# SCH_h_ty_2025829_stm32__2025-11-28.net
KiCad netlist of a schematic drawn in EasyEDA
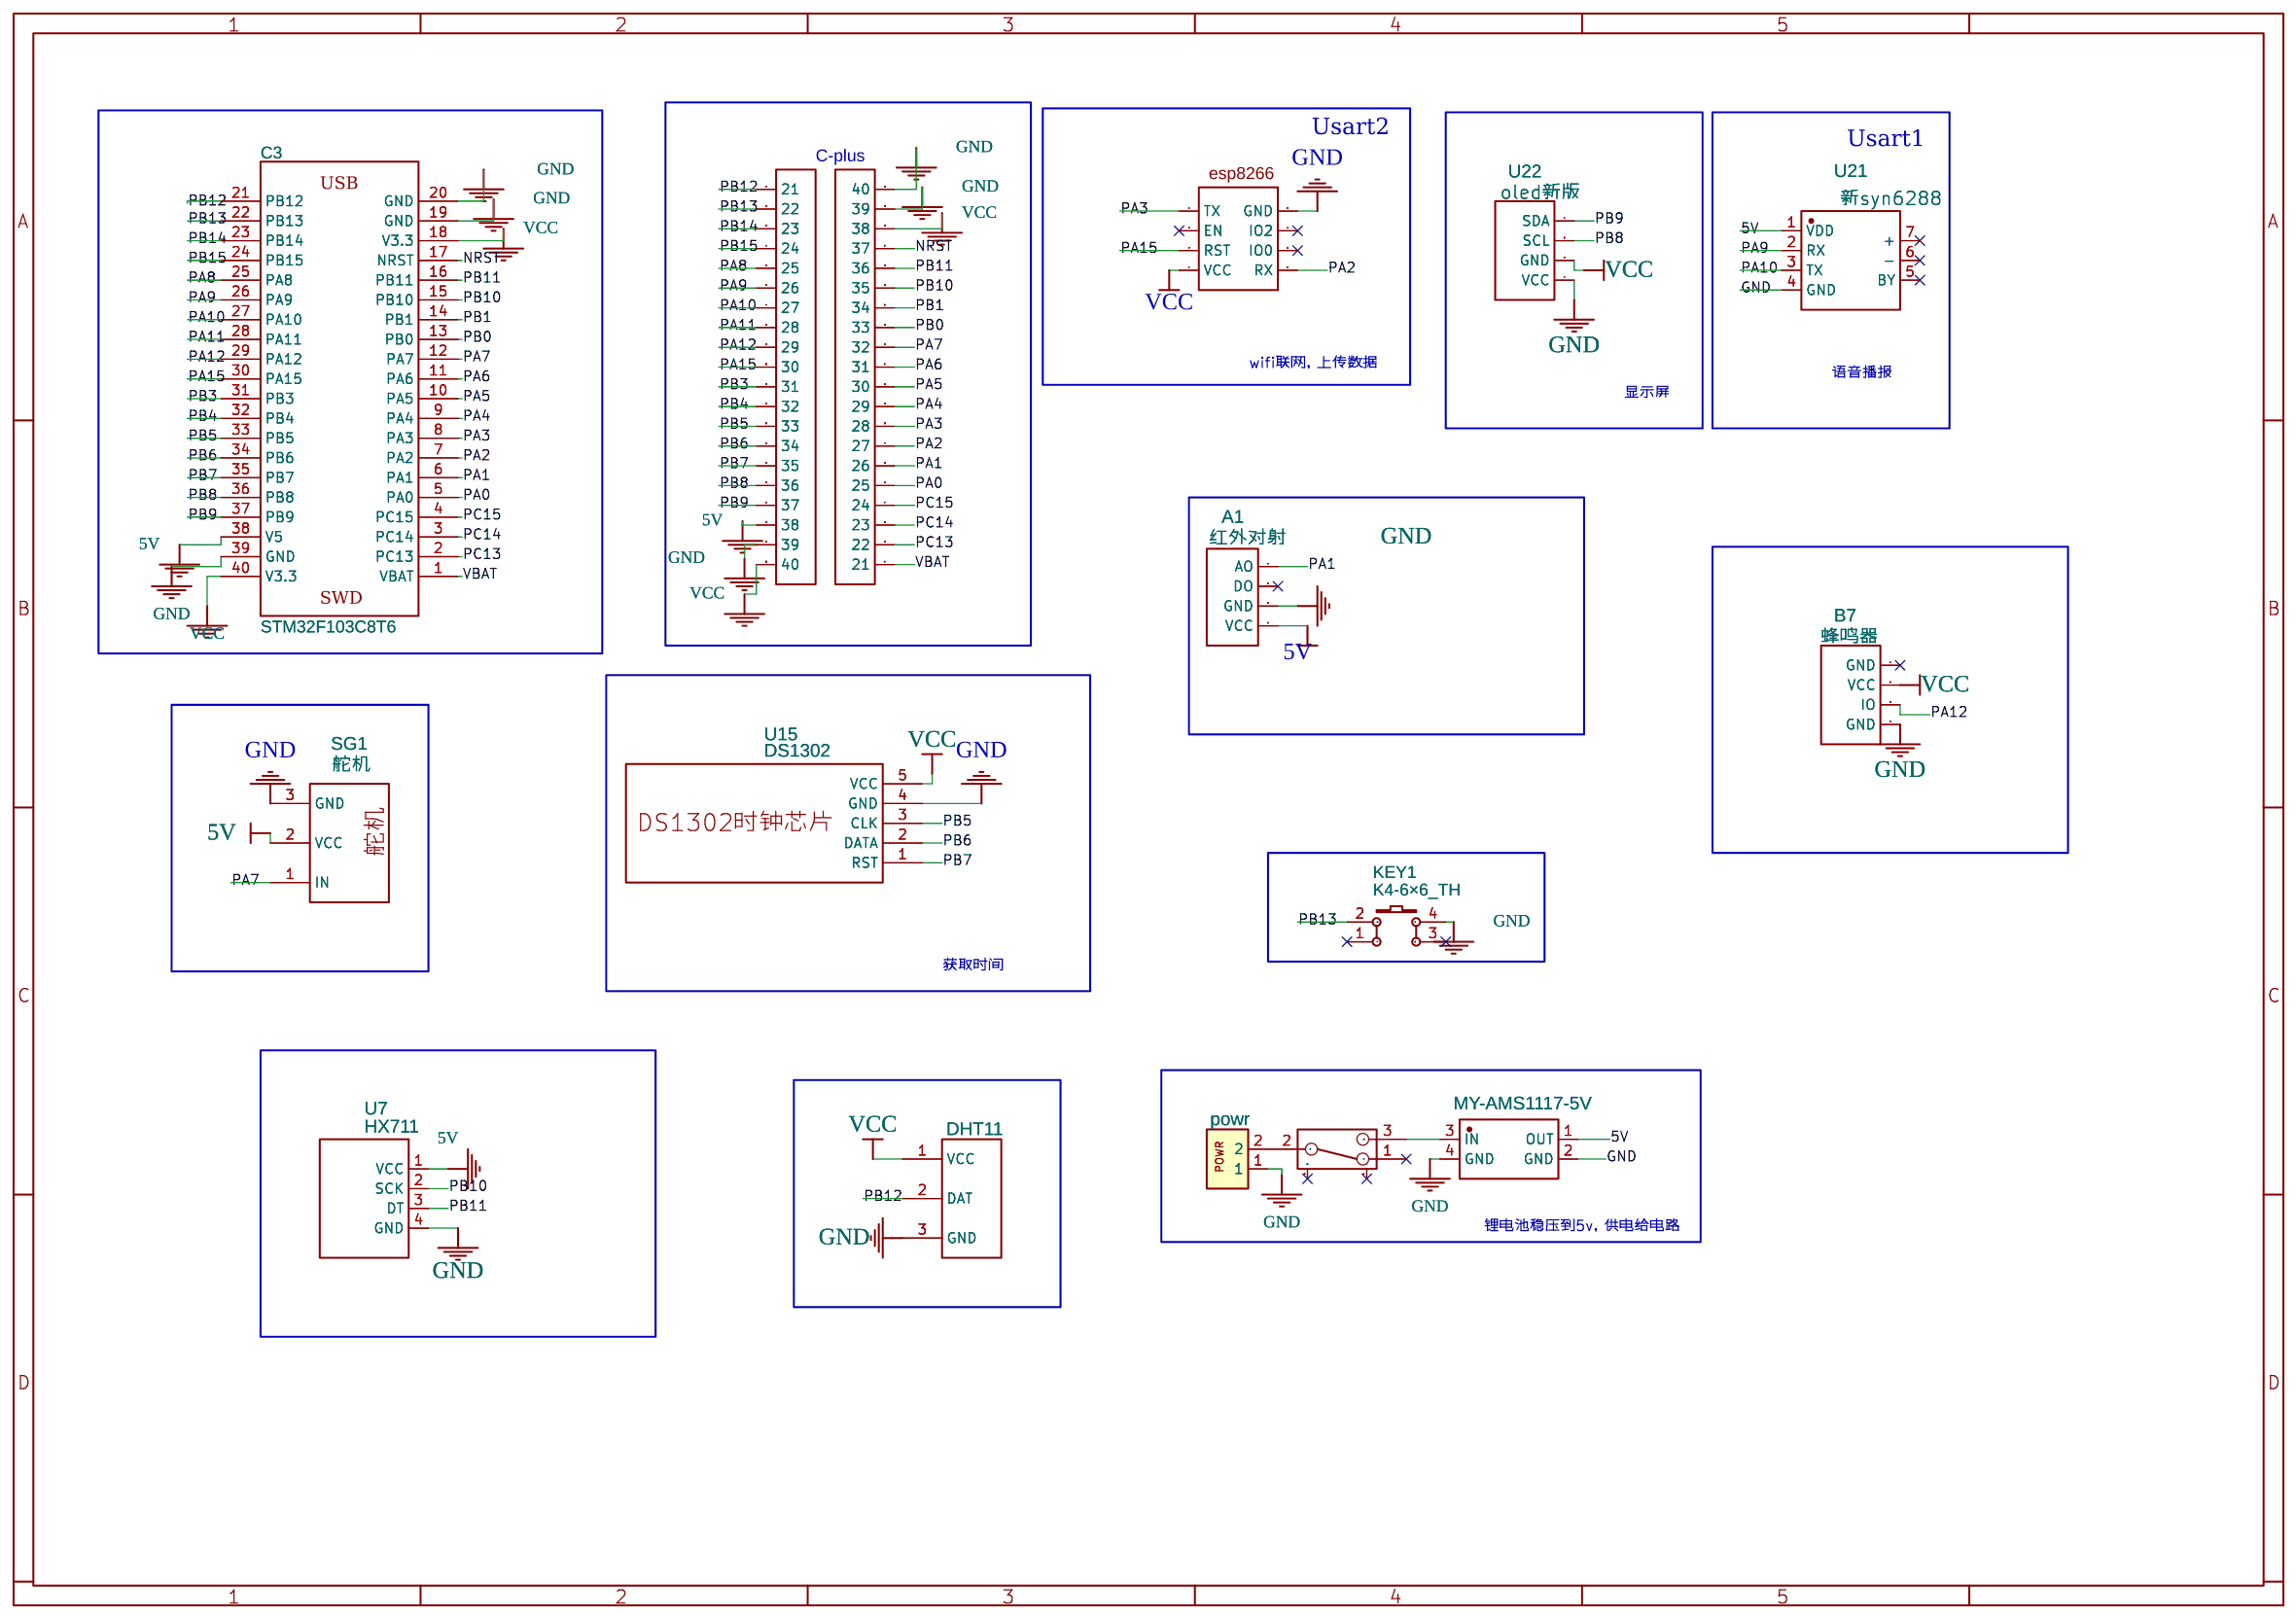
[diagram p0: schematic sheet]

(export (version "E")
  (design (tool "Eeschema 10.0.6"))
  (components
    (comp (ref "A1") (value "红外对射") (libsource (lib "") (part "ADC4P")))
    (comp (ref "B7") (value "蜂鸣器") (libsource (lib "") (part "通用3.3")))
    (comp (ref "C3") (value "STM32F103C8T6") (libsource (lib "") (part "STM32F103C8T6最小系统模块")))
    (comp (ref "DHT11") (value "DHT11模块") (libsource (lib "") (part "DHT11模块")))
    (comp (ref "H2") (value "HDR-F-2.54_1x20") (libsource (lib "") (part "HDR-F-2.54_1x20_1")))
    (comp (ref "H3") (value "HDR-F-2.54_1x20") (libsource (lib "") (part "HDR-F-2.54_1x20")))
    (comp (ref "KEY1")
      (value "K4-6×6_TH")
      (fields (field (name "Manufacturer Part") "K2-1102DP-E4SW-04") (field (name "Manufacturer") "韩国韩荣"))
      (libsource (lib "") (part "K4-6×6_TH"))
    )
    (comp (ref "SG1") (value "舵机") (libsource (lib "") (part "舵机")))
    (comp (ref "SW2")
      (value "SK-12E12-G5")
      (fields (field (name "Manufacturer") "Rectangular Connectors - Contacts"))
      (libsource (lib "") (part "SK-12E12-G5"))
    )
    (comp (ref "U2") (value "powr") (libsource (lib "") (part "powr")))
    (comp (ref "U7") (value "HX711") (libsource (lib "") (part "HX711")))
    (comp (ref "U9") (value "esp8266") (libsource (lib "") (part "esp8266")))
    (comp (ref "U12") (value "MY-AMS1117-5V") (libsource (lib "") (part "MY-AMS1117-5V")))
    (comp (ref "U15") (value "DS1302") (libsource (lib "") (part "DS1302")))
    (comp (ref "U21") (value "新syn6288") (libsource (lib "") (part "新syn6288")))
    (comp (ref "U22") (value "oled新版") (libsource (lib "") (part "HDR-M-2.54_1x4")))
  )
  (nets
    (net (code "1") (name "/NRST") (class "Default")
      (node (ref "C3") (pin "17") (pinfunction "NRST_17") (pintype "unspecified"))
      (node (ref "H3") (pin "17") (pinfunction "37_17") (pintype "unspecified"))
    )
    (net (code "2") (name "/PA0") (class "Default")
      (node (ref "C3") (pin "5") (pinfunction "PA0_5") (pintype "unspecified"))
      (node (ref "H3") (pin "5") (pinfunction "25_5") (pintype "unspecified"))
    )
    (net (code "3") (name "/PA1") (class "Default")
      (node (ref "A1") (pin "4") (pinfunction "AO_4") (pintype "unspecified"))
      (node (ref "C3") (pin "6") (pinfunction "PA1_6") (pintype "unspecified"))
      (node (ref "H3") (pin "6") (pinfunction "26_6") (pintype "unspecified"))
    )
    (net (code "4") (name "/PA2") (class "Default")
      (node (ref "C3") (pin "7") (pinfunction "PA2_7") (pintype "unspecified"))
      (node (ref "H3") (pin "7") (pinfunction "27_7") (pintype "unspecified"))
      (node (ref "U9") (pin "8") (pinfunction "RX_8") (pintype "unspecified"))
    )
    (net (code "5") (name "/PA3") (class "Default")
      (node (ref "C3") (pin "8") (pinfunction "PA3_8") (pintype "unspecified"))
      (node (ref "H3") (pin "8") (pinfunction "28_8") (pintype "unspecified"))
      (node (ref "U9") (pin "1") (pinfunction "TX_1") (pintype "unspecified"))
    )
    (net (code "6") (name "/PA4") (class "Default")
      (node (ref "C3") (pin "9") (pinfunction "PA4_9") (pintype "unspecified"))
      (node (ref "H3") (pin "9") (pinfunction "29_9") (pintype "unspecified"))
    )
    (net (code "7") (name "/PA5") (class "Default")
      (node (ref "C3") (pin "10") (pinfunction "PA5_10") (pintype "unspecified"))
      (node (ref "H3") (pin "10") (pinfunction "30_10") (pintype "unspecified"))
    )
    (net (code "8") (name "/PA6") (class "Default")
      (node (ref "C3") (pin "11") (pinfunction "PA6_11") (pintype "unspecified"))
      (node (ref "H3") (pin "11") (pinfunction "31_11") (pintype "unspecified"))
    )
    (net (code "9") (name "/PA7") (class "Default")
      (node (ref "C3") (pin "12") (pinfunction "PA7_12") (pintype "unspecified"))
      (node (ref "H3") (pin "12") (pinfunction "32_12") (pintype "unspecified"))
      (node (ref "SG1") (pin "1") (pinfunction "IN_1") (pintype "unspecified"))
    )
    (net (code "10") (name "/PA8") (class "Default")
      (node (ref "C3") (pin "25") (pinfunction "PA8_25") (pintype "unspecified"))
      (node (ref "H2") (pin "5") (pinfunction "25_5") (pintype "unspecified"))
    )
    (net (code "11") (name "/PA9") (class "Default")
      (node (ref "C3") (pin "26") (pinfunction "PA9_26") (pintype "unspecified"))
      (node (ref "H2") (pin "6") (pinfunction "26_6") (pintype "unspecified"))
      (node (ref "U21") (pin "2") (pinfunction "RX_2") (pintype "unspecified"))
    )
    (net (code "12") (name "/PA10") (class "Default")
      (node (ref "C3") (pin "27") (pinfunction "PA10_27") (pintype "unspecified"))
      (node (ref "H2") (pin "7") (pinfunction "27_7") (pintype "unspecified"))
      (node (ref "U21") (pin "3") (pinfunction "TX_3") (pintype "unspecified"))
    )
    (net (code "13") (name "/PA11") (class "Default")
      (node (ref "C3") (pin "28") (pinfunction "PA11_28") (pintype "unspecified"))
      (node (ref "H2") (pin "8") (pinfunction "28_8") (pintype "unspecified"))
    )
    (net (code "14") (name "/PA12") (class "Default")
      (node (ref "B7") (pin "2") (pinfunction "IO_2") (pintype "unspecified"))
      (node (ref "C3") (pin "29") (pinfunction "PA12_29") (pintype "unspecified"))
      (node (ref "H2") (pin "9") (pinfunction "29_9") (pintype "unspecified"))
    )
    (net (code "15") (name "/PA15") (class "Default")
      (node (ref "C3") (pin "30") (pinfunction "PA15_30") (pintype "unspecified"))
      (node (ref "H2") (pin "10") (pinfunction "30_10") (pintype "unspecified"))
      (node (ref "U9") (pin "5") (pinfunction "RST_5") (pintype "unspecified"))
    )
    (net (code "16") (name "/PB0") (class "Default")
      (node (ref "C3") (pin "13") (pinfunction "PB0_13") (pintype "unspecified"))
      (node (ref "H3") (pin "13") (pinfunction "33_13") (pintype "unspecified"))
    )
    (net (code "17") (name "/PB1") (class "Default")
      (node (ref "C3") (pin "14") (pinfunction "PB1_14") (pintype "unspecified"))
      (node (ref "H3") (pin "14") (pinfunction "34_14") (pintype "unspecified"))
    )
    (net (code "18") (name "/PB3") (class "Default")
      (node (ref "C3") (pin "31") (pinfunction "PB3_31") (pintype "unspecified"))
      (node (ref "H2") (pin "11") (pinfunction "31_11") (pintype "unspecified"))
    )
    (net (code "19") (name "/PB4") (class "Default")
      (node (ref "C3") (pin "32") (pinfunction "PB4_32") (pintype "unspecified"))
      (node (ref "H2") (pin "12") (pinfunction "32_12") (pintype "unspecified"))
    )
    (net (code "20") (name "/PB5") (class "Default")
      (node (ref "C3") (pin "33") (pinfunction "PB5_33") (pintype "unspecified"))
      (node (ref "H2") (pin "13") (pinfunction "33_13") (pintype "unspecified"))
      (node (ref "U15") (pin "3") (pinfunction "CLK_3") (pintype "unspecified"))
    )
    (net (code "21") (name "/PB6") (class "Default")
      (node (ref "C3") (pin "34") (pinfunction "PB6_34") (pintype "unspecified"))
      (node (ref "H2") (pin "14") (pinfunction "34_14") (pintype "unspecified"))
      (node (ref "U15") (pin "2") (pinfunction "DATA_2") (pintype "unspecified"))
    )
    (net (code "22") (name "/PB7") (class "Default")
      (node (ref "C3") (pin "35") (pinfunction "PB7_35") (pintype "unspecified"))
      (node (ref "H2") (pin "15") (pinfunction "35_15") (pintype "unspecified"))
      (node (ref "U15") (pin "1") (pinfunction "RST_1") (pintype "unspecified"))
    )
    (net (code "23") (name "/PB8") (class "Default")
      (node (ref "C3") (pin "36") (pinfunction "PB8_36") (pintype "unspecified"))
      (node (ref "H2") (pin "16") (pinfunction "36_16") (pintype "unspecified"))
      (node (ref "U22") (pin "3") (pinfunction "SCL_3") (pintype "unspecified"))
    )
    (net (code "24") (name "/PB9") (class "Default")
      (node (ref "C3") (pin "37") (pinfunction "PB9_37") (pintype "unspecified"))
      (node (ref "H2") (pin "17") (pinfunction "37_17") (pintype "unspecified"))
      (node (ref "U22") (pin "4") (pinfunction "SDA_4") (pintype "unspecified"))
    )
    (net (code "25") (name "/PB10") (class "Default")
      (node (ref "C3") (pin "15") (pinfunction "PB10_15") (pintype "unspecified"))
      (node (ref "H3") (pin "15") (pinfunction "35_15") (pintype "unspecified"))
      (node (ref "U7") (pin "2") (pinfunction "SCK_2") (pintype "unspecified"))
    )
    (net (code "26") (name "/PB11") (class "Default")
      (node (ref "C3") (pin "16") (pinfunction "PB11_16") (pintype "unspecified"))
      (node (ref "H3") (pin "16") (pinfunction "36_16") (pintype "unspecified"))
      (node (ref "U7") (pin "3") (pinfunction "DT_3") (pintype "unspecified"))
    )
    (net (code "27") (name "/PB12") (class "Default")
      (node (ref "C3") (pin "21") (pinfunction "PB12_21") (pintype "unspecified"))
      (node (ref "DHT11") (pin "2") (pinfunction "DAT_2") (pintype "unspecified"))
      (node (ref "H2") (pin "1") (pinfunction "21_1") (pintype "unspecified"))
    )
    (net (code "28") (name "/PB13") (class "Default")
      (node (ref "C3") (pin "22") (pinfunction "PB13_22") (pintype "unspecified"))
      (node (ref "H2") (pin "2") (pinfunction "22_2") (pintype "unspecified"))
      (node (ref "KEY1") (pin "2") (pinfunction "2_2") (pintype "unspecified"))
    )
    (net (code "29") (name "/PB14") (class "Default")
      (node (ref "C3") (pin "23") (pinfunction "PB14_23") (pintype "unspecified"))
      (node (ref "H2") (pin "3") (pinfunction "23_3") (pintype "unspecified"))
    )
    (net (code "30") (name "/PB15") (class "Default")
      (node (ref "C3") (pin "24") (pinfunction "PB15_24") (pintype "unspecified"))
      (node (ref "H2") (pin "4") (pinfunction "24_4") (pintype "unspecified"))
    )
    (net (code "31") (name "/PC13") (class "Default")
      (node (ref "C3") (pin "2") (pinfunction "PC13_2") (pintype "unspecified"))
      (node (ref "H3") (pin "2") (pinfunction "22_2") (pintype "unspecified"))
    )
    (net (code "32") (name "/PC14") (class "Default")
      (node (ref "C3") (pin "3") (pinfunction "PC14_3") (pintype "unspecified"))
      (node (ref "H3") (pin "3") (pinfunction "23_3") (pintype "unspecified"))
    )
    (net (code "33") (name "/PC15") (class "Default")
      (node (ref "C3") (pin "4") (pinfunction "PC15_4") (pintype "unspecified"))
      (node (ref "H3") (pin "4") (pinfunction "24_4") (pintype "unspecified"))
    )
    (net (code "34") (name "/VBAT") (class "Default")
      (node (ref "C3") (pin "1") (pinfunction "VBAT_1") (pintype "unspecified"))
      (node (ref "H3") (pin "1") (pinfunction "21_1") (pintype "unspecified"))
    )
    (net (code "35") (name "5V") (class "Default")
      (node (ref "A1") (pin "1") (pinfunction "VCC_1") (pintype "unspecified"))
      (node (ref "C3") (pin "38") (pinfunction "V5_38") (pintype "unspecified"))
      (node (ref "H2") (pin "18") (pinfunction "38_18") (pintype "unspecified"))
      (node (ref "SG1") (pin "2") (pinfunction "VCC_2") (pintype "unspecified"))
      (node (ref "U12") (pin "1") (pinfunction "OUT_1") (pintype "unspecified"))
      (node (ref "U21") (pin "1") (pinfunction "VDD_1") (pintype "unspecified"))
      (node (ref "U7") (pin "1") (pinfunction "VCC_1") (pintype "unspecified"))
    )
    (net (code "36") (name "GND") (class "Default")
      (node (ref "A1") (pin "2") (pinfunction "GND_2") (pintype "unspecified"))
      (node (ref "B7") (pin "1") (pinfunction "GND_1") (pintype "unspecified"))
      (node (ref "C3") (pin "19") (pinfunction "GND_19") (pintype "unspecified"))
      (node (ref "C3") (pin "20") (pinfunction "GND_20") (pintype "unspecified"))
      (node (ref "C3") (pin "39") (pinfunction "GND_39") (pintype "unspecified"))
      (node (ref "DHT11") (pin "3") (pinfunction "GND_3") (pintype "unspecified"))
      (node (ref "H2") (pin "19") (pinfunction "39_19") (pintype "unspecified"))
      (node (ref "H3") (pin "19") (pinfunction "39_19") (pintype "unspecified"))
      (node (ref "H3") (pin "20") (pinfunction "40_20") (pintype "unspecified"))
      (node (ref "KEY1") (pin "4") (pinfunction "4_4") (pintype "unspecified"))
      (node (ref "SG1") (pin "3") (pinfunction "GND_3") (pintype "unspecified"))
      (node (ref "U12") (pin "2") (pinfunction "GND_2") (pintype "unspecified"))
      (node (ref "U12") (pin "4") (pinfunction "GND_4") (pintype "unspecified"))
      (node (ref "U15") (pin "4") (pinfunction "GND_4") (pintype "unspecified"))
      (node (ref "U2") (pin "1") (pinfunction "1_1") (pintype "unspecified"))
      (node (ref "U21") (pin "4") (pinfunction "GND_4") (pintype "unspecified"))
      (node (ref "U22") (pin "1") (pinfunction "VCC_1") (pintype "unspecified"))
      (node (ref "U7") (pin "4") (pinfunction "GND_4") (pintype "unspecified"))
      (node (ref "U9") (pin "2") (pinfunction "GND_2") (pintype "unspecified"))
    )
    (net (code "37") (name "Net-(SW2-Pad2)") (class "Default")
      (node (ref "SW2") (pin "2") (pinfunction "2_2") (pintype "unspecified"))
      (node (ref "U2") (pin "2") (pinfunction "2_2") (pintype "unspecified"))
    )
    (net (code "38") (name "Net-(U12-IN)") (class "Default")
      (node (ref "SW2") (pin "3") (pinfunction "3_3") (pintype "unspecified"))
      (node (ref "U12") (pin "3") (pinfunction "IN_3") (pintype "unspecified"))
    )
    (net (code "39") (name "VCC") (class "Default")
      (node (ref "B7") (pin "3") (pinfunction "VCC_3") (pintype "unspecified"))
      (node (ref "C3") (pin "18") (pinfunction "V3.3_18") (pintype "unspecified"))
      (node (ref "C3") (pin "40") (pinfunction "V3.3_40") (pintype "unspecified"))
      (node (ref "DHT11") (pin "1") (pinfunction "VCC_1") (pintype "unspecified"))
      (node (ref "H2") (pin "20") (pinfunction "40_20") (pintype "unspecified"))
      (node (ref "H3") (pin "18") (pinfunction "38_18") (pintype "unspecified"))
      (node (ref "U15") (pin "5") (pinfunction "VCC_5") (pintype "unspecified"))
      (node (ref "U22") (pin "2") (pinfunction "GND_2") (pintype "unspecified"))
      (node (ref "U9") (pin "7") (pinfunction "VCC_7") (pintype "unspecified"))
    )
    (net (code "40") (name "unconnected-(A1-DO-Pad3)") (class "Default")
      (node (ref "A1") (pin "3") (pinfunction "DO_3") (pintype "unspecified+no_connect"))
    )
    (net (code "41") (name "unconnected-(B7-GND-Pad4)") (class "Default")
      (node (ref "B7") (pin "4") (pinfunction "GND_4") (pintype "unspecified+no_connect"))
    )
    (net (code "42") (name "unconnected-(KEY1-Pad1)") (class "Default")
      (node (ref "KEY1") (pin "1") (pinfunction "1_1") (pintype "unspecified+no_connect"))
    )
    (net (code "43") (name "unconnected-(KEY1-Pad3)") (class "Default")
      (node (ref "KEY1") (pin "3") (pinfunction "3_3") (pintype "unspecified+no_connect"))
    )
    (net (code "44") (name "unconnected-(SW2-Pad1)") (class "Default")
      (node (ref "SW2") (pin "1") (pinfunction "1_1") (pintype "unspecified+no_connect"))
    )
    (net (code "45") (name "unconnected-(SW2-Pad4)") (class "Default")
      (node (ref "SW2") (pin "4") (pinfunction "4_4") (pintype "unspecified+no_connect"))
    )
    (net (code "46") (name "unconnected-(SW2-Pad5)") (class "Default")
      (node (ref "SW2") (pin "5") (pinfunction "5_5") (pintype "unspecified+no_connect"))
    )
    (net (code "47") (name "unconnected-(U9-EN-Pad3)") (class "Default")
      (node (ref "U9") (pin "3") (pinfunction "EN_3") (pintype "unspecified+no_connect"))
    )
    (net (code "48") (name "unconnected-(U9-IO0-Pad6)") (class "Default")
      (node (ref "U9") (pin "6") (pinfunction "IO0_6") (pintype "unspecified+no_connect"))
    )
    (net (code "49") (name "unconnected-(U9-IO2-Pad4)") (class "Default")
      (node (ref "U9") (pin "4") (pinfunction "IO2_4") (pintype "unspecified+no_connect"))
    )
    (net (code "50") (name "unconnected-(U21-+-Pad7)") (class "Default")
      (node (ref "U21") (pin "7") (pinfunction "+_7") (pintype "unspecified+no_connect"))
    )
    (net (code "51") (name "unconnected-(U21---Pad6)") (class "Default")
      (node (ref "U21") (pin "6") (pinfunction "-_6") (pintype "unspecified+no_connect"))
    )
    (net (code "52") (name "unconnected-(U21-BY-Pad5)") (class "Default")
      (node (ref "U21") (pin "5") (pinfunction "BY_5") (pintype "unspecified+no_connect"))
    )
  )
)
